# untitled.net
KiCad netlist of a schematic drawn in EAGLE
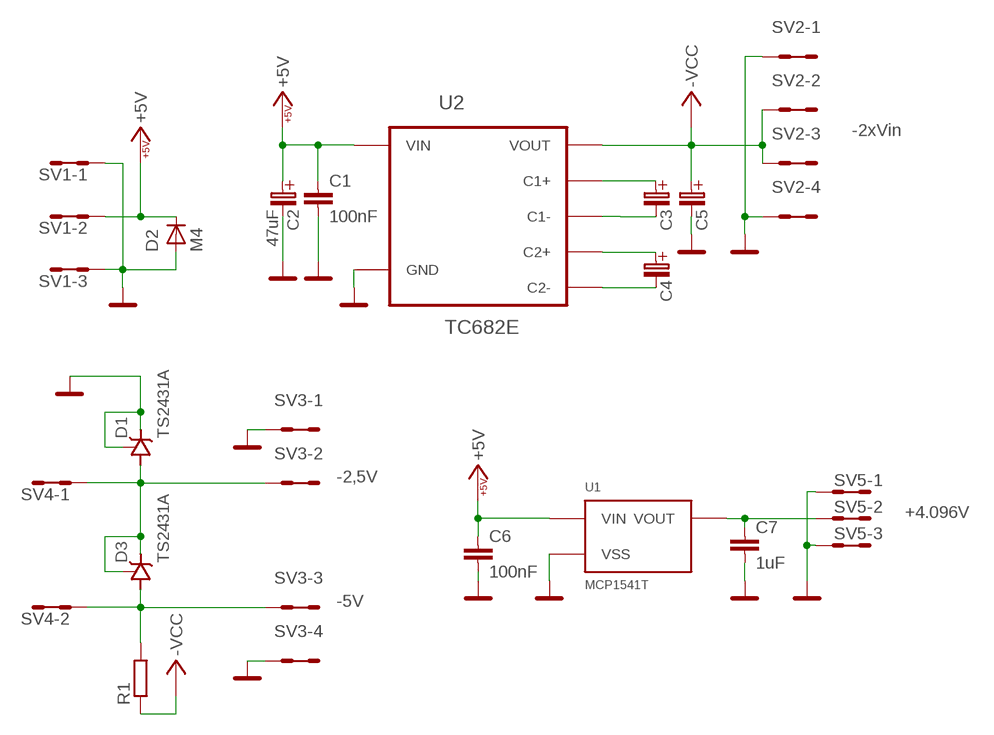
[diagram p0: schematic, sheet 1]

(export (version "E")
  (design (tool "Eeschema 10.0.6"))
  (components
    (comp (ref "C1")
      (value "100nF")
      (footprint "eagle-import:C0805")
      (libsource (lib "eagle-import") (part "C0805"))
    )
    (comp (ref "C2") (value "47uF") (footprint "eagle-import:C") (libsource (lib "eagle-import") (part "C")))
    (comp (ref "C3") (value "C") (footprint "eagle-import:C") (libsource (lib "eagle-import") (part "C")))
    (comp (ref "C4") (value "C") (footprint "eagle-import:C") (libsource (lib "eagle-import") (part "C")))
    (comp (ref "C5") (value "C") (footprint "eagle-import:C") (libsource (lib "eagle-import") (part "C")))
    (comp (ref "C6")
      (value "100nF")
      (footprint "eagle-import:C0805")
      (libsource (lib "eagle-import") (part "C0805"))
    )
    (comp (ref "C7")
      (value "1uF")
      (footprint "eagle-import:C0805")
      (libsource (lib "eagle-import") (part "C0805"))
    )
    (comp (ref "D1")
      (value "TS2431A")
      (footprint "eagle-import:SOT23")
      (libsource (lib "eagle-import") (part "TS2431A"))
    )
    (comp (ref "D2")
      (value "M4")
      (footprint "eagle-import:SMA")
      (libsource (lib "eagle-import") (part "D-OB.SMA"))
    )
    (comp (ref "D3")
      (value "TS2431A")
      (footprint "eagle-import:SOT23")
      (libsource (lib "eagle-import") (part "TS2431A"))
    )
    (comp (ref "R1")
      (value "R0805")
      (footprint "eagle-import:0805")
      (libsource (lib "eagle-import") (part "R0805"))
    )
    (comp (ref "SV1")
      (value "MA03-2")
      (footprint "eagle-import:MA03-2")
      (libsource (lib "eagle-import") (part "MA03-2"))
    )
    (comp (ref "SV2")
      (value "MA04-2")
      (footprint "eagle-import:MA04-2")
      (libsource (lib "eagle-import") (part "MA04-2"))
    )
    (comp (ref "SV3")
      (value "MA04-2")
      (footprint "eagle-import:MA04-2")
      (libsource (lib "eagle-import") (part "MA04-2"))
    )
    (comp (ref "SV4")
      (value "MA02-2")
      (footprint "eagle-import:MA02-2")
      (libsource (lib "eagle-import") (part "MA02-2"))
    )
    (comp (ref "SV5")
      (value "MA03-2")
      (footprint "eagle-import:MA03-2")
      (libsource (lib "eagle-import") (part "MA03-2"))
    )
    (comp (ref "U1")
      (value "MCP1541T")
      (footprint "eagle-import:SOT23")
      (libsource (lib "eagle-import") (part "MCP1541T"))
    )
    (comp (ref "U2")
      (value "TC682E")
      (footprint "eagle-import:SO8")
      (libsource (lib "eagle-import") (part "TC682"))
    )
  )
  (nets
    (net (code "1") (name "+5V") (class "Default")
      (node (ref "C1") (pin "1") (pinfunction "1_1") (pintype "passive"))
      (node (ref "C2") (pin "+") (pinfunction "C_EL+_+") (pintype "passive"))
      (node (ref "C6") (pin "1") (pinfunction "1_1") (pintype "passive"))
      (node (ref "D2") (pin "K") (pinfunction "C_K") (pintype "passive"))
      (node (ref "SV1") (pin "3") (pinfunction "K_3") (pintype "passive"))
      (node (ref "SV1") (pin "4") (pinfunction "K_4") (pintype "passive"))
      (node (ref "U1") (pin "1") (pinfunction "VIN_1") (pintype "bidirectional"))
      (node (ref "U2") (pin "6") (pinfunction "VIN_6") (pintype "bidirectional"))
    )
    (net (code "2") (name "-VCC") (class "Default")
      (node (ref "C5") (pin "+") (pinfunction "C_EL+_+") (pintype "passive"))
      (node (ref "R1") (pin "1") (pinfunction "1_1") (pintype "passive"))
      (node (ref "SV2") (pin "3") (pinfunction "K_3") (pintype "passive"))
      (node (ref "SV2") (pin "4") (pinfunction "K_4") (pintype "passive"))
      (node (ref "SV2") (pin "5") (pinfunction "K_5") (pintype "passive"))
      (node (ref "SV2") (pin "6") (pinfunction "K_6") (pintype "passive"))
      (node (ref "U2") (pin "4") (pinfunction "VOUT_4") (pintype "bidirectional"))
    )
    (net (code "3") (name "GND") (class "Default")
      (node (ref "C1") (pin "2") (pinfunction "2_2") (pintype "passive"))
      (node (ref "C2") (pin "-") (pinfunction "C_EL-_-") (pintype "passive"))
      (node (ref "C5") (pin "-") (pinfunction "C_EL-_-") (pintype "passive"))
      (node (ref "C6") (pin "2") (pinfunction "2_2") (pintype "passive"))
      (node (ref "C7") (pin "2") (pinfunction "2_2") (pintype "passive"))
      (node (ref "D1") (pin "1") (pinfunction "K_1") (pintype "passive"))
      (node (ref "D1") (pin "2") (pinfunction "P$1_2") (pintype "passive"))
      (node (ref "D2") (pin "A") (pinfunction "A_A") (pintype "passive"))
      (node (ref "SV1") (pin "1") (pinfunction "K_1") (pintype "passive"))
      (node (ref "SV1") (pin "2") (pinfunction "K_2") (pintype "passive"))
      (node (ref "SV1") (pin "5") (pinfunction "K_5") (pintype "passive"))
      (node (ref "SV1") (pin "6") (pinfunction "K_6") (pintype "passive"))
      (node (ref "SV2") (pin "1") (pinfunction "K_1") (pintype "passive"))
      (node (ref "SV2") (pin "2") (pinfunction "K_2") (pintype "passive"))
      (node (ref "SV2") (pin "7") (pinfunction "K_7") (pintype "passive"))
      (node (ref "SV2") (pin "8") (pinfunction "K_8") (pintype "passive"))
      (node (ref "SV3") (pin "1") (pinfunction "K_1") (pintype "passive"))
      (node (ref "SV3") (pin "2") (pinfunction "K_2") (pintype "passive"))
      (node (ref "SV3") (pin "7") (pinfunction "K_7") (pintype "passive"))
      (node (ref "SV3") (pin "8") (pinfunction "K_8") (pintype "passive"))
      (node (ref "SV5") (pin "1") (pinfunction "K_1") (pintype "passive"))
      (node (ref "SV5") (pin "2") (pinfunction "K_2") (pintype "passive"))
      (node (ref "SV5") (pin "5") (pinfunction "K_5") (pintype "passive"))
      (node (ref "SV5") (pin "6") (pinfunction "K_6") (pintype "passive"))
      (node (ref "U1") (pin "3") (pinfunction "VSS_3") (pintype "bidirectional"))
      (node (ref "U2") (pin "5") (pinfunction "GND_5") (pintype "bidirectional"))
    )
    (net (code "4") (name "Net-(C3-C_EL+)") (class "Default")
      (node (ref "C3") (pin "+") (pinfunction "C_EL+_+") (pintype "passive"))
      (node (ref "U2") (pin "7") (pinfunction "C1+_7") (pintype "bidirectional"))
    )
    (net (code "5") (name "Net-(C3-C_EL-)") (class "Default")
      (node (ref "C3") (pin "-") (pinfunction "C_EL-_-") (pintype "passive"))
      (node (ref "U2") (pin "1") (pinfunction "C1-_1") (pintype "bidirectional"))
    )
    (net (code "6") (name "Net-(C4-C_EL+)") (class "Default")
      (node (ref "C4") (pin "+") (pinfunction "C_EL+_+") (pintype "passive"))
      (node (ref "U2") (pin "2") (pinfunction "C2+_2") (pintype "bidirectional"))
    )
    (net (code "7") (name "Net-(C4-C_EL-)") (class "Default")
      (node (ref "C4") (pin "-") (pinfunction "C_EL-_-") (pintype "passive"))
      (node (ref "U2") (pin "3") (pinfunction "C2-_3") (pintype "bidirectional"))
    )
    (net (code "8") (name "Net-(D1-A)") (class "Default")
      (node (ref "D1") (pin "3") (pinfunction "A_3") (pintype "passive"))
      (node (ref "D3") (pin "1") (pinfunction "K_1") (pintype "passive"))
      (node (ref "D3") (pin "2") (pinfunction "P$1_2") (pintype "passive"))
      (node (ref "SV3") (pin "3") (pinfunction "K_3") (pintype "passive"))
      (node (ref "SV3") (pin "4") (pinfunction "K_4") (pintype "passive"))
      (node (ref "SV4") (pin "1") (pinfunction "K_1") (pintype "passive"))
      (node (ref "SV4") (pin "2") (pinfunction "K_2") (pintype "passive"))
    )
    (net (code "9") (name "Net-(D3-A)") (class "Default")
      (node (ref "D3") (pin "3") (pinfunction "A_3") (pintype "passive"))
      (node (ref "R1") (pin "2") (pinfunction "2_2") (pintype "passive"))
      (node (ref "SV3") (pin "5") (pinfunction "K_5") (pintype "passive"))
      (node (ref "SV3") (pin "6") (pinfunction "K_6") (pintype "passive"))
      (node (ref "SV4") (pin "3") (pinfunction "K_3") (pintype "passive"))
      (node (ref "SV4") (pin "4") (pinfunction "K_4") (pintype "passive"))
    )
    (net (code "10") (name "Net-(U1-VOUT)") (class "Default")
      (node (ref "C7") (pin "1") (pinfunction "1_1") (pintype "passive"))
      (node (ref "SV5") (pin "3") (pinfunction "K_3") (pintype "passive"))
      (node (ref "SV5") (pin "4") (pinfunction "K_4") (pintype "passive"))
      (node (ref "U1") (pin "2") (pinfunction "VOUT_2") (pintype "bidirectional"))
    )
  )
)
